# Motor.net
KiCad netlist of a schematic drawn in Altium Designer
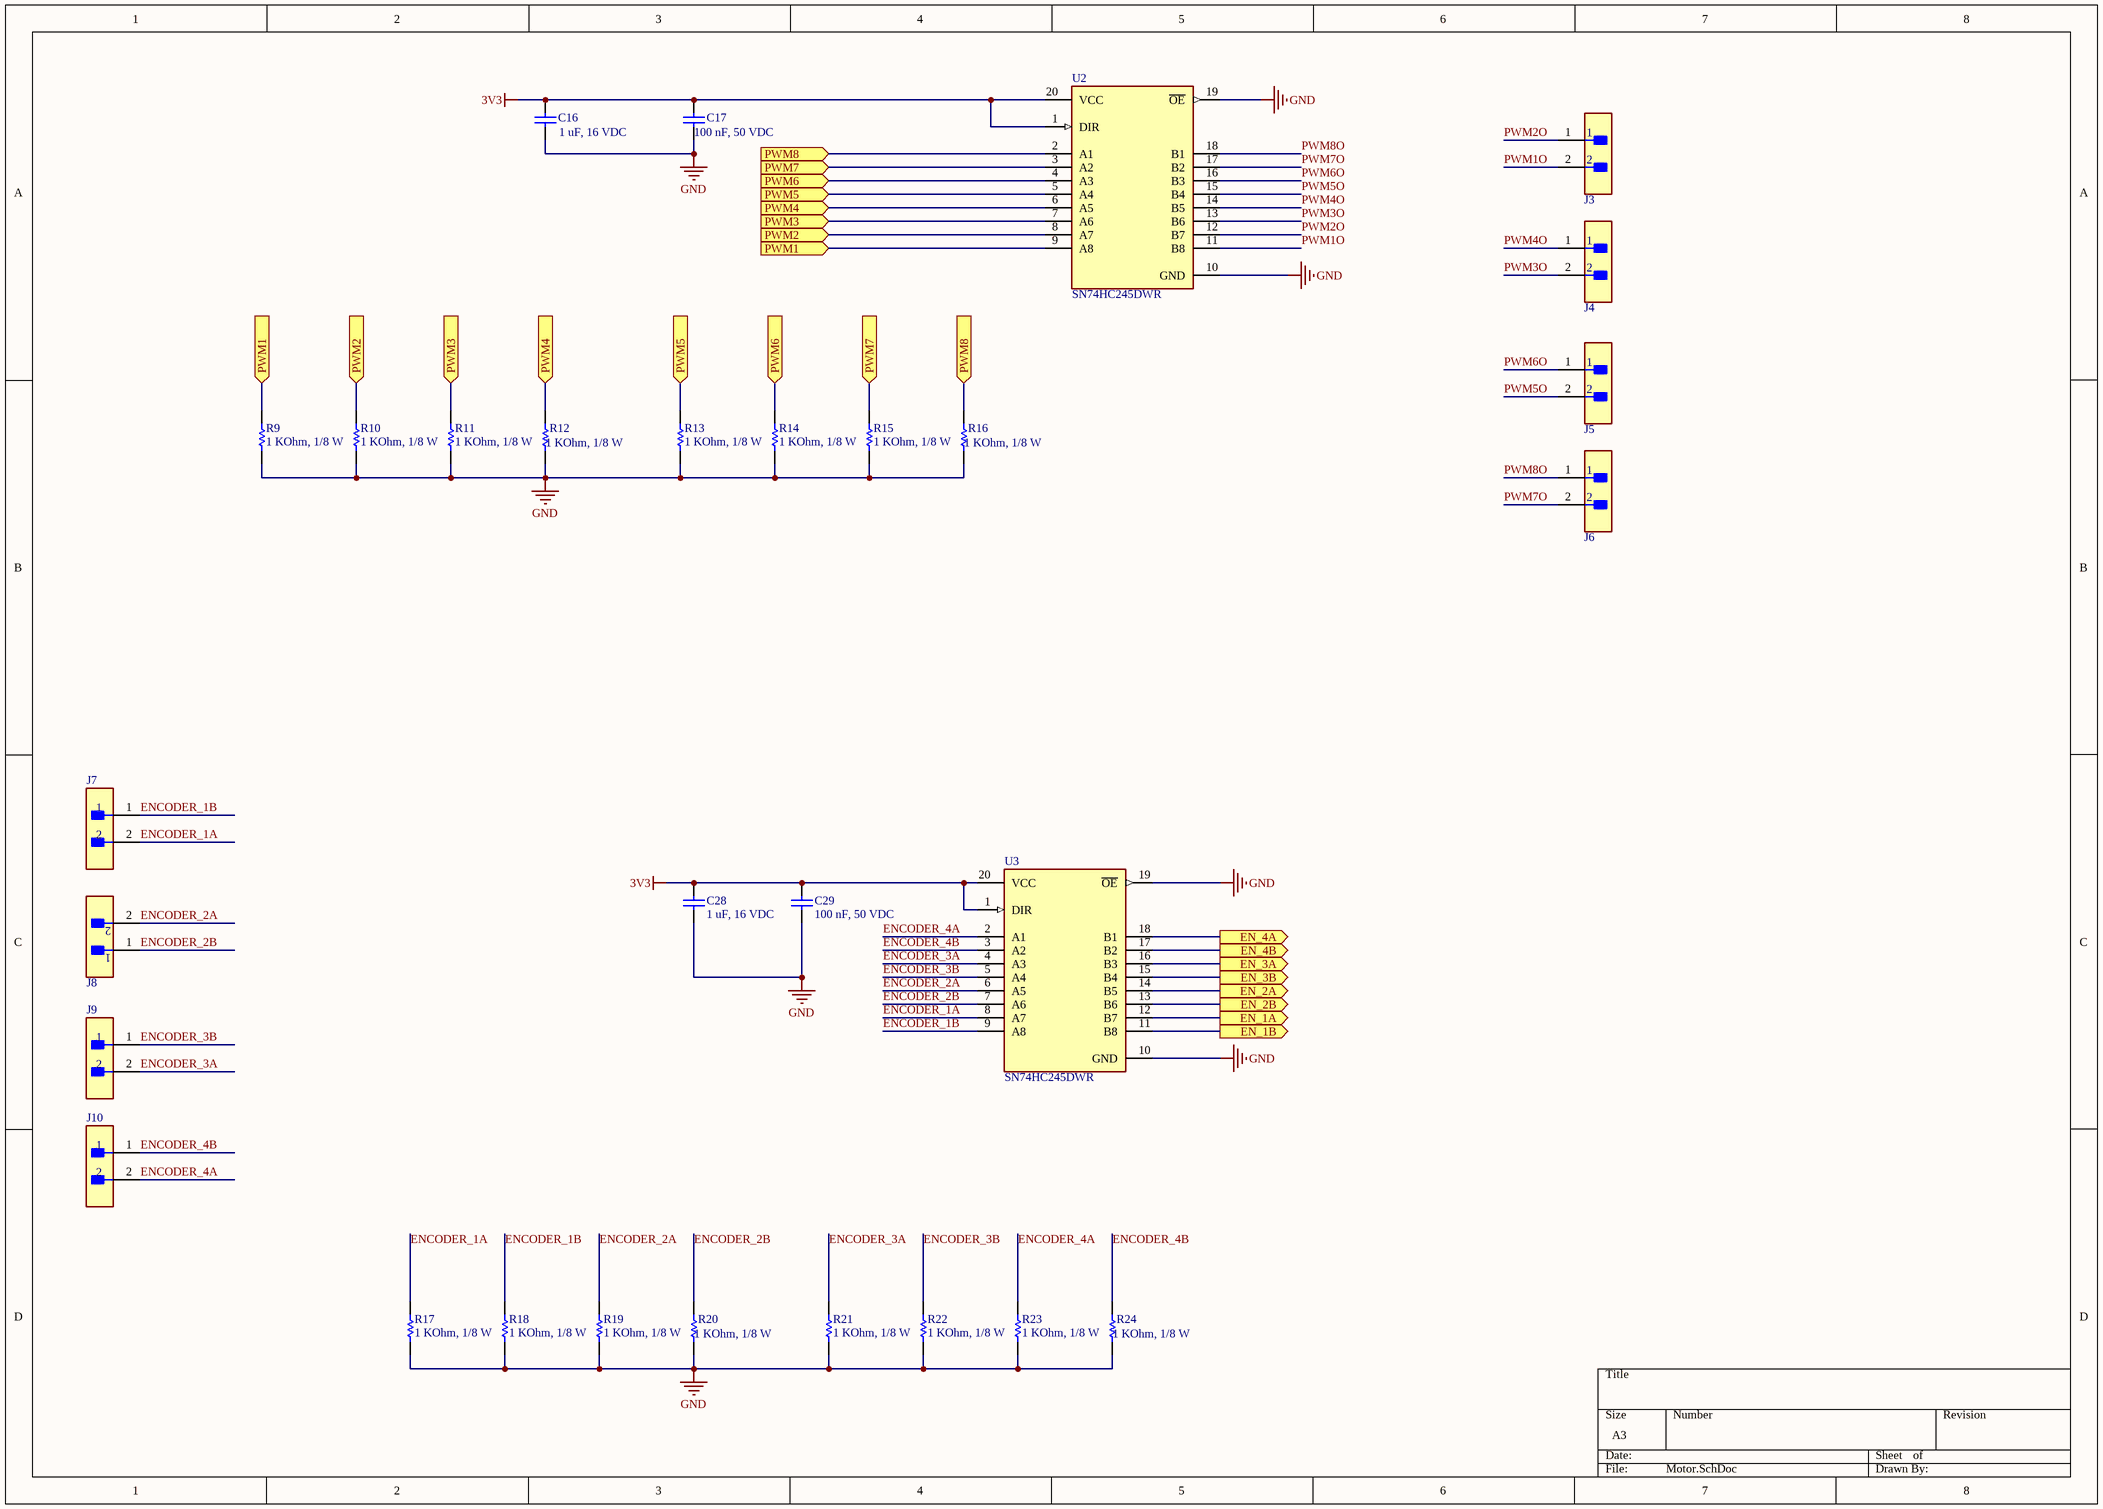
[diagram p0: Motor.SchDoc]

(export (version "E")
  (design (tool "Eeschema 10.0.6"))
  (components
    (comp (ref "C16")
      (value "1 uF, 16 VDC")
      (footprint "CAP_0603")
      (description "CAP, size 0603, 1 uF, 16 VDC")
      (fields (field (name "TOLERANCE") "+/-10%"))
      (libsource (lib "Altium_Ceramic_Cap") (part "0106031051016"))
    )
    (comp (ref "C17")
      (value "100 nF, 50 VDC")
      (footprint "CAP_0603")
      (description "CAP, size 0603, 100 nF, 50 VDC")
      (fields (field (name "TOLERANCE") "+/-10%"))
      (libsource (lib "Altium_Ceramic_Cap") (part "0106031041050"))
    )
    (comp (ref "C28")
      (value "1 uF, 16 VDC")
      (footprint "CAP_0805")
      (description "CAP, size 0805, 1 uF, 16 VDC")
      (fields (field (name "TOLERANCE") "+/-10%"))
      (libsource (lib "Altium_Ceramic_Cap") (part "0108051051016"))
    )
    (comp (ref "C29")
      (value "100 nF, 50 VDC")
      (footprint "CAP_0805")
      (description "CAP, size 0805, 100 nF, 50 VDC")
      (fields (field (name "TOLERANCE") "+/-5%"))
      (libsource (lib "Altium_Ceramic_Cap") (part "0108051031050"))
    )
    (comp (ref "J3")
      (value "B2B-XH-A(LF)(SN)")
      (footprint "FP-B2B-XH-A_LF_SN-MFG")
      (description "CONN HEADER VERT 2POS 2.5MM")
      (libsource (lib "Altium Content Vault") (part "3bc925449376181038e59eaffc5286c"))
    )
    (comp (ref "J4")
      (value "B2B-XH-A(LF)(SN)")
      (footprint "FP-B2B-XH-A_LF_SN-MFG")
      (description "CONN HEADER VERT 2POS 2.5MM")
      (libsource (lib "Altium Content Vault") (part "3bc925449376181038e59eaffc5286c"))
    )
    (comp (ref "J5")
      (value "B2B-XH-A(LF)(SN)")
      (footprint "FP-B2B-XH-A_LF_SN-MFG")
      (description "CONN HEADER VERT 2POS 2.5MM")
      (libsource (lib "Altium Content Vault") (part "3bc925449376181038e59eaffc5286c"))
    )
    (comp (ref "J6")
      (value "B2B-XH-A(LF)(SN)")
      (footprint "FP-B2B-XH-A_LF_SN-MFG")
      (description "CONN HEADER VERT 2POS 2.5MM")
      (libsource (lib "Altium Content Vault") (part "3bc925449376181038e59eaffc5286c"))
    )
    (comp (ref "J7")
      (value "B2B-XH-A(LF)(SN)")
      (footprint "FP-B2B-XH-A_LF_SN-MFG")
      (description "CONN HEADER VERT 2POS 2.5MM")
      (libsource (lib "") (part "3bc925449376181038e59eaffc5286c_1"))
    )
    (comp (ref "J8")
      (value "B2B-XH-A(LF)(SN)")
      (footprint "FP-B2B-XH-A_LF_SN-MFG")
      (description "CONN HEADER VERT 2POS 2.5MM")
      (libsource (lib "") (part "3bc925449376181038e59eaffc5286c_2"))
    )
    (comp (ref "J9")
      (value "B2B-XH-A(LF)(SN)")
      (footprint "FP-B2B-XH-A_LF_SN-MFG")
      (description "CONN HEADER VERT 2POS 2.5MM")
      (libsource (lib "") (part "3bc925449376181038e59eaffc5286c_1"))
    )
    (comp (ref "J10")
      (value "B2B-XH-A(LF)(SN)")
      (footprint "FP-B2B-XH-A_LF_SN-MFG")
      (description "CONN HEADER VERT 2POS 2.5MM")
      (libsource (lib "") (part "3bc925449376181038e59eaffc5286c_1"))
    )
    (comp (ref "R9")
      (value "1 KOhm, 1/8 W")
      (footprint "RESISTOR_0805")
      (description "RES, size 0805, 1 KOhm, 1/8 W")
      (libsource (lib "Altium_Resistor") (part "0008051021"))
    )
    (comp (ref "R10")
      (value "1 KOhm, 1/8 W")
      (footprint "RESISTOR_0805")
      (description "RES, size 0805, 1 KOhm, 1/8 W")
      (libsource (lib "Altium_Resistor") (part "0008051021"))
    )
    (comp (ref "R11")
      (value "1 KOhm, 1/8 W")
      (footprint "RESISTOR_0805")
      (description "RES, size 0805, 1 KOhm, 1/8 W")
      (libsource (lib "Altium_Resistor") (part "0008051021"))
    )
    (comp (ref "R12")
      (value "1 KOhm, 1/8 W")
      (footprint "RESISTOR_0805")
      (description "RES, size 0805, 1 KOhm, 1/8 W")
      (libsource (lib "Altium_Resistor") (part "0008051021"))
    )
    (comp (ref "R13")
      (value "1 KOhm, 1/8 W")
      (footprint "RESISTOR_0805")
      (description "RES, size 0805, 1 KOhm, 1/8 W")
      (libsource (lib "Altium_Resistor") (part "0008051021"))
    )
    (comp (ref "R14")
      (value "1 KOhm, 1/8 W")
      (footprint "RESISTOR_0805")
      (description "RES, size 0805, 1 KOhm, 1/8 W")
      (libsource (lib "Altium_Resistor") (part "0008051021"))
    )
    (comp (ref "R15")
      (value "1 KOhm, 1/8 W")
      (footprint "RESISTOR_0805")
      (description "RES, size 0805, 1 KOhm, 1/8 W")
      (libsource (lib "Altium_Resistor") (part "0008051021"))
    )
    (comp (ref "R16")
      (value "1 KOhm, 1/8 W")
      (footprint "RESISTOR_0805")
      (description "RES, size 0805, 1 KOhm, 1/8 W")
      (libsource (lib "Altium_Resistor") (part "0008051021"))
    )
    (comp (ref "R17")
      (value "1 KOhm, 1/8 W")
      (footprint "RESISTOR_0805")
      (description "RES, size 0805, 1 KOhm, 1/8 W")
      (libsource (lib "Altium_Resistor") (part "0008051021"))
    )
    (comp (ref "R18")
      (value "1 KOhm, 1/8 W")
      (footprint "RESISTOR_0805")
      (description "RES, size 0805, 1 KOhm, 1/8 W")
      (libsource (lib "Altium_Resistor") (part "0008051021"))
    )
    (comp (ref "R19")
      (value "1 KOhm, 1/8 W")
      (footprint "RESISTOR_0805")
      (description "RES, size 0805, 1 KOhm, 1/8 W")
      (libsource (lib "Altium_Resistor") (part "0008051021"))
    )
    (comp (ref "R20")
      (value "1 KOhm, 1/8 W")
      (footprint "RESISTOR_0805")
      (description "RES, size 0805, 1 KOhm, 1/8 W")
      (libsource (lib "Altium_Resistor") (part "0008051021"))
    )
    (comp (ref "R21")
      (value "1 KOhm, 1/8 W")
      (footprint "RESISTOR_0805")
      (description "RES, size 0805, 1 KOhm, 1/8 W")
      (libsource (lib "Altium_Resistor") (part "0008051021"))
    )
    (comp (ref "R22")
      (value "1 KOhm, 1/8 W")
      (footprint "RESISTOR_0805")
      (description "RES, size 0805, 1 KOhm, 1/8 W")
      (libsource (lib "Altium_Resistor") (part "0008051021"))
    )
    (comp (ref "R23")
      (value "1 KOhm, 1/8 W")
      (footprint "RESISTOR_0805")
      (description "RES, size 0805, 1 KOhm, 1/8 W")
      (libsource (lib "Altium_Resistor") (part "0008051021"))
    )
    (comp (ref "R24")
      (value "1 KOhm, 1/8 W")
      (footprint "RESISTOR_0805")
      (description "RES, size 0805, 1 KOhm, 1/8 W")
      (libsource (lib "Altium_Resistor") (part "0008051021"))
    )
    (comp (ref "U2")
      (value "SN74HC245DWR")
      (footprint "FP-DW0020A-IPC_A")
      (description "IC TRANSCVR NON-INVERT 6V 20SOIC")
      (libsource (lib "Altium Content Vault") (part "88901bc343d40937cf0e66f0656714f"))
    )
    (comp (ref "U3")
      (value "SN74HC245DWR")
      (footprint "FP-DW0020A-IPC_A")
      (description "IC TRANSCVR NON-INVERT 6V 20SOIC")
      (libsource (lib "Altium Content Vault") (part "88901bc343d40937cf0e66f0656714f"))
    )
  )
  (nets
    (net (code "1") (name "/ENCODER_1A") (class "Default")
      (node (ref "J7") (pin "2") (pinfunction "2_2") (pintype "passive"))
      (node (ref "R17") (pin "2") (pinfunction "2_2") (pintype "passive"))
      (node (ref "U3") (pin "8") (pinfunction "A7_8") (pintype "passive"))
    )
    (net (code "2") (name "/ENCODER_1B") (class "Default")
      (node (ref "J7") (pin "1") (pinfunction "1_1") (pintype "passive"))
      (node (ref "R18") (pin "2") (pinfunction "2_2") (pintype "passive"))
      (node (ref "U3") (pin "9") (pinfunction "A8_9") (pintype "passive"))
    )
    (net (code "3") (name "/ENCODER_2A") (class "Default")
      (node (ref "J8") (pin "2") (pinfunction "2_2") (pintype "passive"))
      (node (ref "R19") (pin "2") (pinfunction "2_2") (pintype "passive"))
      (node (ref "U3") (pin "6") (pinfunction "A5_6") (pintype "passive"))
    )
    (net (code "4") (name "/ENCODER_2B") (class "Default")
      (node (ref "J8") (pin "1") (pinfunction "1_1") (pintype "passive"))
      (node (ref "R20") (pin "2") (pinfunction "2_2") (pintype "passive"))
      (node (ref "U3") (pin "7") (pinfunction "A6_7") (pintype "passive"))
    )
    (net (code "5") (name "/ENCODER_3A") (class "Default")
      (node (ref "J9") (pin "2") (pinfunction "2_2") (pintype "passive"))
      (node (ref "R21") (pin "2") (pinfunction "2_2") (pintype "passive"))
      (node (ref "U3") (pin "4") (pinfunction "A3_4") (pintype "passive"))
    )
    (net (code "6") (name "/ENCODER_3B") (class "Default")
      (node (ref "J9") (pin "1") (pinfunction "1_1") (pintype "passive"))
      (node (ref "R22") (pin "2") (pinfunction "2_2") (pintype "passive"))
      (node (ref "U3") (pin "5") (pinfunction "A4_5") (pintype "passive"))
    )
    (net (code "7") (name "/ENCODER_4A") (class "Default")
      (node (ref "J10") (pin "2") (pinfunction "2_2") (pintype "passive"))
      (node (ref "R23") (pin "2") (pinfunction "2_2") (pintype "passive"))
      (node (ref "U3") (pin "2") (pinfunction "A1_2") (pintype "passive"))
    )
    (net (code "8") (name "/ENCODER_4B") (class "Default")
      (node (ref "J10") (pin "1") (pinfunction "1_1") (pintype "passive"))
      (node (ref "R24") (pin "2") (pinfunction "2_2") (pintype "passive"))
      (node (ref "U3") (pin "3") (pinfunction "A2_3") (pintype "passive"))
    )
    (net (code "9") (name "/EN_1A") (class "Default")
      (node (ref "U3") (pin "12") (pinfunction "B7_12") (pintype "passive"))
    )
    (net (code "10") (name "/EN_1B") (class "Default")
      (node (ref "U3") (pin "11") (pinfunction "B8_11") (pintype "passive"))
    )
    (net (code "11") (name "/EN_2A") (class "Default")
      (node (ref "U3") (pin "14") (pinfunction "B5_14") (pintype "passive"))
    )
    (net (code "12") (name "/EN_2B") (class "Default")
      (node (ref "U3") (pin "13") (pinfunction "B6_13") (pintype "passive"))
    )
    (net (code "13") (name "/EN_3A") (class "Default")
      (node (ref "U3") (pin "16") (pinfunction "B3_16") (pintype "passive"))
    )
    (net (code "14") (name "/EN_3B") (class "Default")
      (node (ref "U3") (pin "15") (pinfunction "B4_15") (pintype "passive"))
    )
    (net (code "15") (name "/EN_4A") (class "Default")
      (node (ref "U3") (pin "18") (pinfunction "B1_18") (pintype "passive"))
    )
    (net (code "16") (name "/EN_4B") (class "Default")
      (node (ref "U3") (pin "17") (pinfunction "B2_17") (pintype "passive"))
    )
    (net (code "17") (name "/PWM1") (class "Default")
      (node (ref "R9") (pin "2") (pinfunction "2_2") (pintype "passive"))
      (node (ref "U2") (pin "9") (pinfunction "A8_9") (pintype "passive"))
    )
    (net (code "18") (name "/PWM1O") (class "Default")
      (node (ref "J3") (pin "2") (pinfunction "2_2") (pintype "passive"))
      (node (ref "U2") (pin "11") (pinfunction "B8_11") (pintype "passive"))
    )
    (net (code "19") (name "/PWM2") (class "Default")
      (node (ref "R10") (pin "2") (pinfunction "2_2") (pintype "passive"))
      (node (ref "U2") (pin "8") (pinfunction "A7_8") (pintype "passive"))
    )
    (net (code "20") (name "/PWM2O") (class "Default")
      (node (ref "J3") (pin "1") (pinfunction "1_1") (pintype "passive"))
      (node (ref "U2") (pin "12") (pinfunction "B7_12") (pintype "passive"))
    )
    (net (code "21") (name "/PWM3") (class "Default")
      (node (ref "R11") (pin "2") (pinfunction "2_2") (pintype "passive"))
      (node (ref "U2") (pin "7") (pinfunction "A6_7") (pintype "passive"))
    )
    (net (code "22") (name "/PWM3O") (class "Default")
      (node (ref "J4") (pin "2") (pinfunction "2_2") (pintype "passive"))
      (node (ref "U2") (pin "13") (pinfunction "B6_13") (pintype "passive"))
    )
    (net (code "23") (name "/PWM4") (class "Default")
      (node (ref "R12") (pin "2") (pinfunction "2_2") (pintype "passive"))
      (node (ref "U2") (pin "6") (pinfunction "A5_6") (pintype "passive"))
    )
    (net (code "24") (name "/PWM4O") (class "Default")
      (node (ref "J4") (pin "1") (pinfunction "1_1") (pintype "passive"))
      (node (ref "U2") (pin "14") (pinfunction "B5_14") (pintype "passive"))
    )
    (net (code "25") (name "/PWM5") (class "Default")
      (node (ref "R13") (pin "2") (pinfunction "2_2") (pintype "passive"))
      (node (ref "U2") (pin "5") (pinfunction "A4_5") (pintype "passive"))
    )
    (net (code "26") (name "/PWM5O") (class "Default")
      (node (ref "J5") (pin "2") (pinfunction "2_2") (pintype "passive"))
      (node (ref "U2") (pin "15") (pinfunction "B4_15") (pintype "passive"))
    )
    (net (code "27") (name "/PWM6") (class "Default")
      (node (ref "R14") (pin "2") (pinfunction "2_2") (pintype "passive"))
      (node (ref "U2") (pin "4") (pinfunction "A3_4") (pintype "passive"))
    )
    (net (code "28") (name "/PWM6O") (class "Default")
      (node (ref "J5") (pin "1") (pinfunction "1_1") (pintype "passive"))
      (node (ref "U2") (pin "16") (pinfunction "B3_16") (pintype "passive"))
    )
    (net (code "29") (name "/PWM7") (class "Default")
      (node (ref "R15") (pin "2") (pinfunction "2_2") (pintype "passive"))
      (node (ref "U2") (pin "3") (pinfunction "A2_3") (pintype "passive"))
    )
    (net (code "30") (name "/PWM7O") (class "Default")
      (node (ref "J6") (pin "2") (pinfunction "2_2") (pintype "passive"))
      (node (ref "U2") (pin "17") (pinfunction "B2_17") (pintype "passive"))
    )
    (net (code "31") (name "/PWM8") (class "Default")
      (node (ref "R16") (pin "2") (pinfunction "2_2") (pintype "passive"))
      (node (ref "U2") (pin "2") (pinfunction "A1_2") (pintype "passive"))
    )
    (net (code "32") (name "/PWM8O") (class "Default")
      (node (ref "J6") (pin "1") (pinfunction "1_1") (pintype "passive"))
      (node (ref "U2") (pin "18") (pinfunction "B1_18") (pintype "passive"))
    )
    (net (code "33") (name "3V3") (class "Default")
      (node (ref "C16") (pin "2") (pinfunction "2_2") (pintype "passive"))
      (node (ref "C17") (pin "2") (pinfunction "2_2") (pintype "passive"))
      (node (ref "C28") (pin "2") (pinfunction "2_2") (pintype "passive"))
      (node (ref "C29") (pin "2") (pinfunction "2_2") (pintype "passive"))
      (node (ref "U2") (pin "1") (pinfunction "DIR_1") (pintype "input"))
      (node (ref "U2") (pin "20") (pinfunction "VCC_20") (pintype "open_emitter"))
      (node (ref "U3") (pin "1") (pinfunction "DIR_1") (pintype "input"))
      (node (ref "U3") (pin "20") (pinfunction "VCC_20") (pintype "open_emitter"))
    )
    (net (code "34") (name "GND") (class "Default")
      (node (ref "C16") (pin "1") (pinfunction "1_1") (pintype "passive"))
      (node (ref "C17") (pin "1") (pinfunction "1_1") (pintype "passive"))
      (node (ref "C28") (pin "1") (pinfunction "1_1") (pintype "passive"))
      (node (ref "C29") (pin "1") (pinfunction "1_1") (pintype "passive"))
      (node (ref "R10") (pin "1") (pinfunction "1_1") (pintype "passive"))
      (node (ref "R11") (pin "1") (pinfunction "1_1") (pintype "passive"))
      (node (ref "R12") (pin "1") (pinfunction "1_1") (pintype "passive"))
      (node (ref "R13") (pin "1") (pinfunction "1_1") (pintype "passive"))
      (node (ref "R14") (pin "1") (pinfunction "1_1") (pintype "passive"))
      (node (ref "R15") (pin "1") (pinfunction "1_1") (pintype "passive"))
      (node (ref "R16") (pin "1") (pinfunction "1_1") (pintype "passive"))
      (node (ref "R17") (pin "1") (pinfunction "1_1") (pintype "passive"))
      (node (ref "R18") (pin "1") (pinfunction "1_1") (pintype "passive"))
      (node (ref "R19") (pin "1") (pinfunction "1_1") (pintype "passive"))
      (node (ref "R20") (pin "1") (pinfunction "1_1") (pintype "passive"))
      (node (ref "R21") (pin "1") (pinfunction "1_1") (pintype "passive"))
      (node (ref "R22") (pin "1") (pinfunction "1_1") (pintype "passive"))
      (node (ref "R23") (pin "1") (pinfunction "1_1") (pintype "passive"))
      (node (ref "R24") (pin "1") (pinfunction "1_1") (pintype "passive"))
      (node (ref "R9") (pin "1") (pinfunction "1_1") (pintype "passive"))
      (node (ref "U2") (pin "10") (pinfunction "GND_10") (pintype "power_in"))
      (node (ref "U2") (pin "19") (pinfunction "~{OE}_19") (pintype "output"))
      (node (ref "U3") (pin "10") (pinfunction "GND_10") (pintype "power_in"))
      (node (ref "U3") (pin "19") (pinfunction "~{OE}_19") (pintype "output"))
    )
  )
)
